# PD_MK2_Connectors.net
KiCad netlist of a schematic drawn in Altium Designer
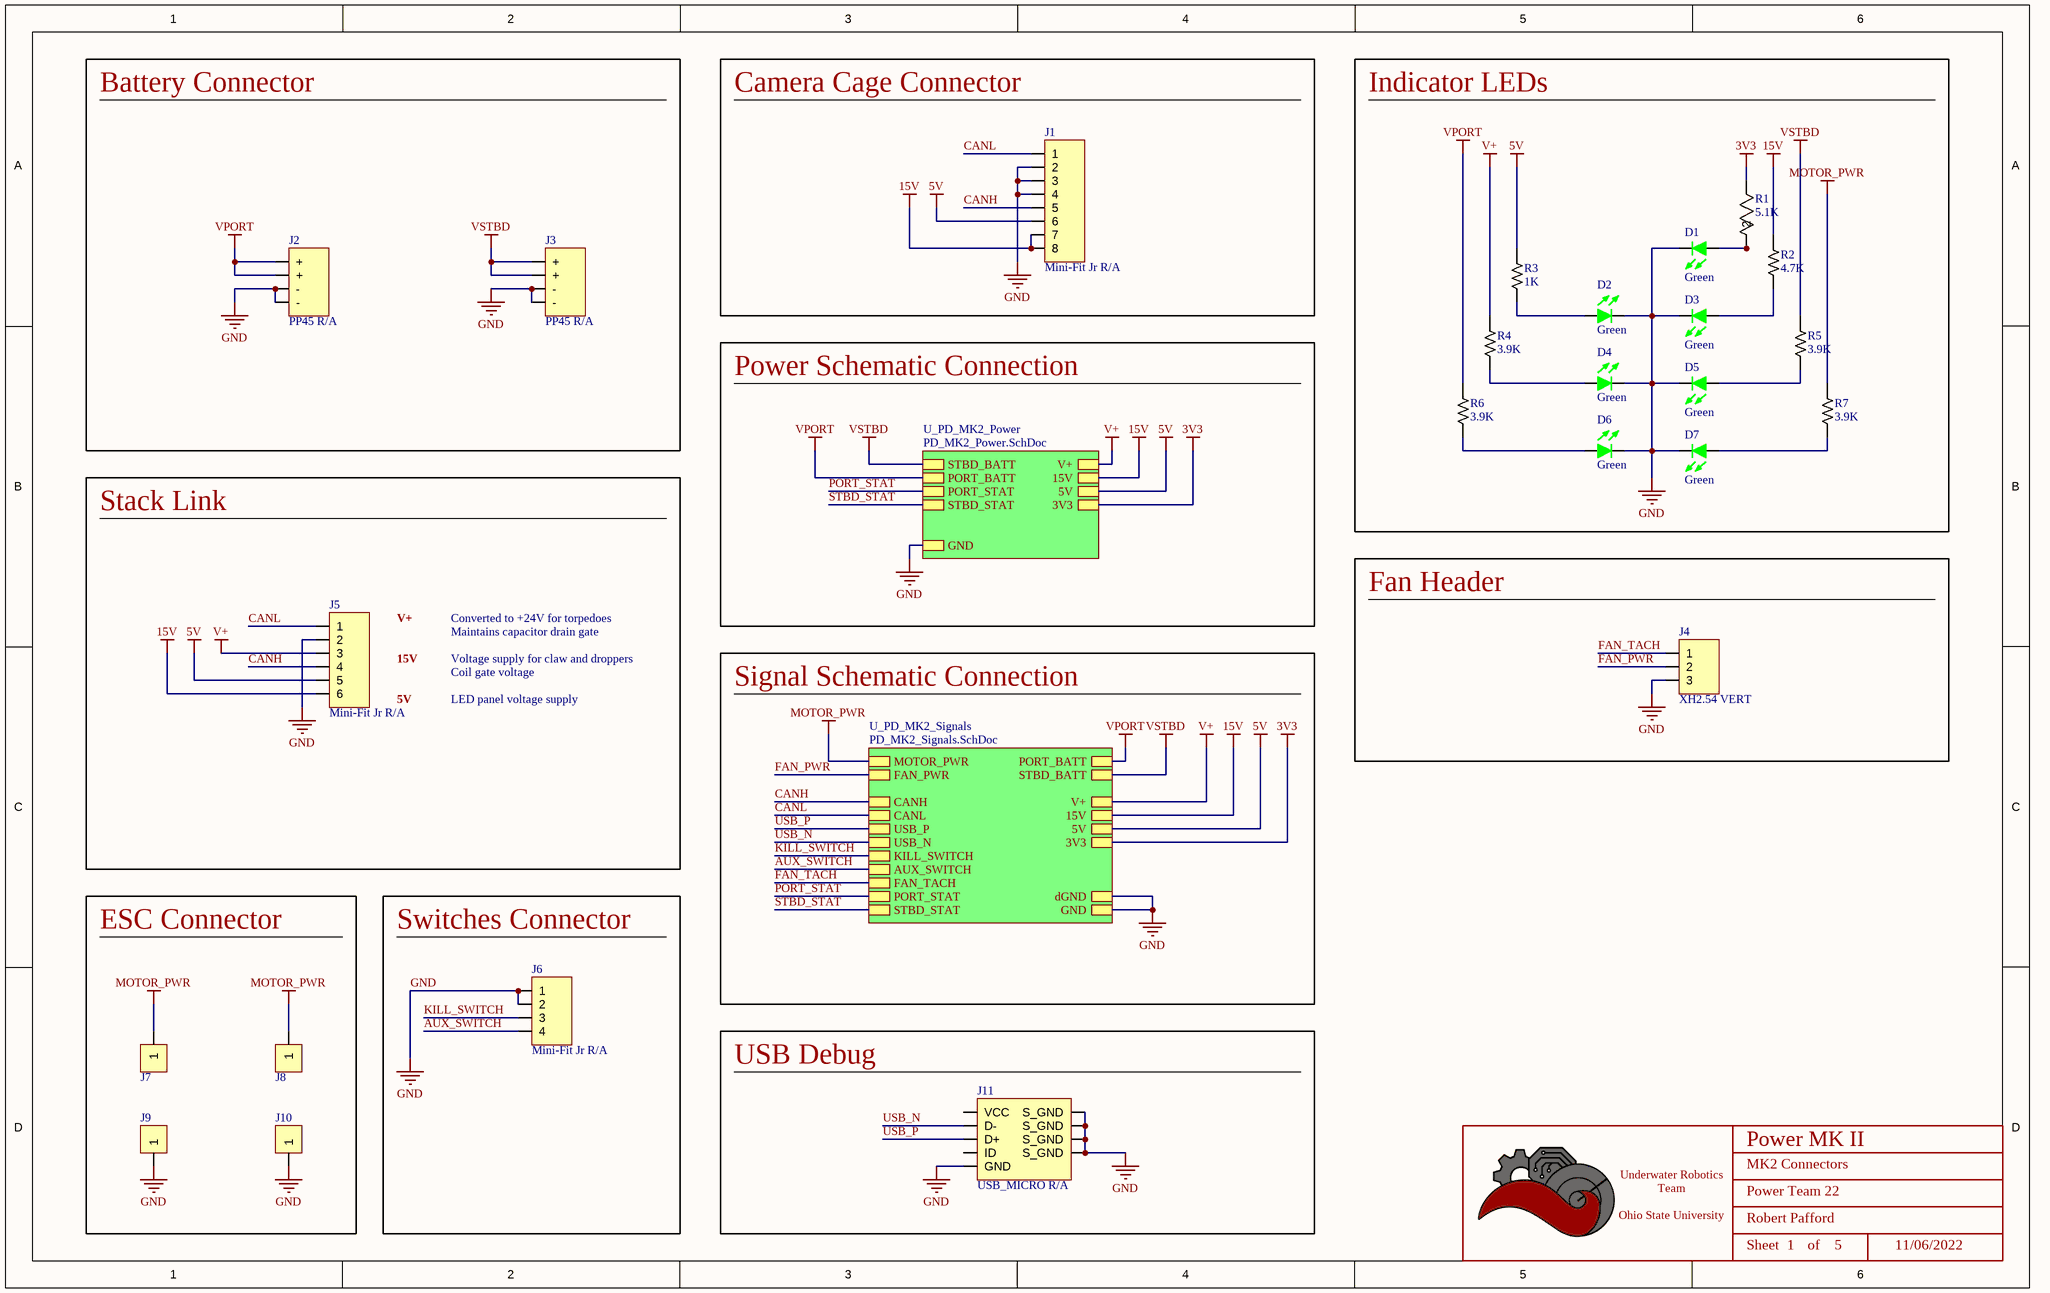
[diagram p0: PD_MK2_Connectors.SchDoc]

(export (version "E")
  (design (tool "Eeschema 10.0.6"))
  (components
    (comp (ref "D1")
      (value "IN-S63AT5G")
      (footprint "LED_0603")
      (description "LED Green Vf= 3V If = 0.005A\r\nIN-S63AT5G")
      (fields (field (name "COLOR") "Green") (field (name "MADE BY") "Robert Pafford"))
      (libsource (lib "Diodes") (part "LED_Green_0603_3V"))
    )
    (comp (ref "D2")
      (value "IN-S63AT5G")
      (footprint "LED_0603")
      (description "LED Green Vf= 3V If = 0.005A\r\nIN-S63AT5G")
      (fields (field (name "COLOR") "Green") (field (name "MADE BY") "Robert Pafford"))
      (libsource (lib "Diodes") (part "LED_Green_0603_3V"))
    )
    (comp (ref "D3")
      (value "IN-S63AT5G")
      (footprint "LED_0603")
      (description "LED Green Vf= 3V If = 0.005A\r\nIN-S63AT5G")
      (fields (field (name "COLOR") "Green") (field (name "MADE BY") "Robert Pafford"))
      (libsource (lib "Diodes") (part "LED_Green_0603_3V"))
    )
    (comp (ref "D4")
      (value "IN-S63AT5G")
      (footprint "LED_0603")
      (description "LED Green Vf= 3V If = 0.005A\r\nIN-S63AT5G")
      (fields (field (name "COLOR") "Green") (field (name "MADE BY") "Robert Pafford"))
      (libsource (lib "Diodes") (part "LED_Green_0603_3V"))
    )
    (comp (ref "D5")
      (value "IN-S63AT5G")
      (footprint "LED_0603")
      (description "LED Green Vf= 3V If = 0.005A\r\nIN-S63AT5G")
      (fields (field (name "COLOR") "Green") (field (name "MADE BY") "Robert Pafford"))
      (libsource (lib "Diodes") (part "LED_Green_0603_3V"))
    )
    (comp (ref "D6")
      (value "IN-S63AT5G")
      (footprint "LED_0603")
      (description "LED Green Vf= 3V If = 0.005A\r\nIN-S63AT5G")
      (fields (field (name "COLOR") "Green") (field (name "MADE BY") "Robert Pafford"))
      (libsource (lib "Diodes") (part "LED_Green_0603_3V"))
    )
    (comp (ref "D7")
      (value "IN-S63AT5G")
      (footprint "LED_0603")
      (description "LED Green Vf= 3V If = 0.005A\r\nIN-S63AT5G")
      (fields (field (name "COLOR") "Green") (field (name "MADE BY") "Robert Pafford"))
      (libsource (lib "Diodes") (part "LED_Green_0603_3V"))
    )
    (comp (ref "J1")
      (value "Mini-Fit Jr R/A")
      (footprint "CONN_MOLEX_MINIFIT JR_8 POS_R/A")
      (description "Molex Minifit Jr. 5569 \r\n8 Pos R/A Natural")
      (fields (field (name "MANUFACTURER") "Molex") (field (name "CREATED BY") "Flip B"))
      (libsource (lib "Connectors") (part "CONN_MOLEX_MINIFIT JR_8POS_R/A"))
    )
    (comp (ref "J2")
      (value "PP45 R/A")
      (footprint "CONN_ANDERSON_PP45_4 POS_R/A")
      (description "Anderson PP45\r\n4 Pos R/A Red/Black")
      (fields (field (name "MANUFACTURER") "Anderson") (field (name "CREATED BY") "Flip B"))
      (libsource (lib "Connectors") (part "CONN_ANDERSON_2x2_R/A"))
    )
    (comp (ref "J3")
      (value "PP45 R/A")
      (footprint "CONN_ANDERSON_PP45_4 POS_R/A")
      (description "Anderson PP45\r\n4 Pos R/A Red/Black")
      (fields (field (name "MANUFACTURER") "Anderson") (field (name "CREATED BY") "Flip B"))
      (libsource (lib "Connectors") (part "CONN_ANDERSON_2x2_R/A"))
    )
    (comp (ref "J4")
      (value "XH2.54 VERT")
      (footprint "CONN_JST_XH254_3POS_VERT")
      (description "JST XH 2.54mm Pitch 3 Pos Vertical")
      (fields (field (name "MANUFACTURER") "JST") (field (name "CREATED BY") "Robert P"))
      (libsource (lib "Connectors") (part "CONN_JST_XH254_3POS_VERT"))
    )
    (comp (ref "J5")
      (value "Mini-Fit Jr R/A")
      (footprint "CONN_MOLEX_MINIFIT JR_6 POS_R/A")
      (description "Molex Minifit Jr. 5569 \r\n6 Pos R/A Natural")
      (fields (field (name "MANUFACTURER") "Molex") (field (name "CREATED BY") "Flip B"))
      (libsource (lib "Connectors") (part "CONN_MOLEX_MINIFIT JR_6POS_R/A"))
    )
    (comp (ref "J6")
      (value "Mini-Fit Jr R/A")
      (footprint "CONN_MOLEX_MINIFIT JR_4 POS_R/A")
      (description "Molex Minifit Jr. 5569 \r\n4 Pos R/A Natural")
      (fields (field (name "MANUFACTURER") "Molex") (field (name "CREATED BY") "Flip B"))
      (libsource (lib "Connectors") (part "CONN_MOLEX_MINIFIT JR_4POS_R/A"))
    )
    (comp (ref "J7")
      (value "Redcube M4 Term 85A")
      (footprint "Redcube M4 Term 85A")
      (fields (field (name "CREATED BY") "Nahtan Ayer"))
      (libsource (lib "") (part "Redcube M4 Term 85A_1"))
    )
    (comp (ref "J8")
      (value "Redcube M4 Term 85A")
      (footprint "Redcube M4 Term 85A")
      (fields (field (name "CREATED BY") "Nahtan Ayer"))
      (libsource (lib "") (part "Redcube M4 Term 85A_1"))
    )
    (comp (ref "J9")
      (value "Redcube M4 Term 85A")
      (footprint "Redcube M4 Term 85A")
      (fields (field (name "CREATED BY") "Nahtan Ayer"))
      (libsource (lib "Connectors") (part "Redcube M4 Term 85A"))
    )
    (comp (ref "J10")
      (value "Redcube M4 Term 85A")
      (footprint "Redcube M4 Term 85A")
      (fields (field (name "CREATED BY") "Nahtan Ayer"))
      (libsource (lib "Connectors") (part "Redcube M4 Term 85A"))
    )
    (comp (ref "J11")
      (value "USB_MICRO R/A")
      (footprint "CONN_MINIUSB")
      (description "Amphenol Micro USB-B\r\nUSB2.0 5 Pin Right Angle SMD")
      (fields (field (name "MANUFACTURER") "Amphenol") (field (name "CREATED BY") "Flip B"))
      (libsource (lib "Connectors") (part "CONN_MICROUSB"))
    )
    (comp (ref "R1")
      (value "5.1K")
      (footprint "RC0603N_PAN")
      (description "5.1 kOhms ±0.1% 0.1W, 1/10W Chip Resistor 0603 (1608 Metric) Automotive AEC-Q200 Thin Film")
      (fields
        (field (name "MANUFACTURER_PART_NUMBER") "ERA-3AEB512V_2")
        (field (name "COPYRIGHT") "Copyright (C) 2023 Ultra Librarian. All rights reserved.")
      )
      (libsource (lib "Resistors") (part "ERA-3AEB512V_2"))
    )
    (comp (ref "R2")
      (value "4.7k Ohm 5% 1/10W")
      (footprint "RESISTOR_0603")
      (description "RES 4.7k OHM 5% 1/10W 0603")
      (fields
        (field (name "TOLERANCE") "+/- 5%")
        (field (name "VALUE  (OHMS)") "4.7K")
        (field (name "MADE BY") "Robert Pafford")
      )
      (libsource (lib "Resistors") (part "RESISTOR_4.7K_0603"))
    )
    (comp (ref "R3")
      (value "1k Ohm 5% 1/8W")
      (footprint "RESISTOR_0603")
      (description "RES 1k OHM 5% 1/8W 0603")
      (fields
        (field (name "TOLERANCE") "+/- 5%")
        (field (name "VALUE  (OHMS)") "1K")
        (field (name "MADE BY") "Robert Pafford")
      )
      (libsource (lib "Resistors") (part "RESISTOR_1K_0603"))
    )
    (comp (ref "R4")
      (value "3.9k Ohm 5% 1/10W")
      (footprint "RESISTOR_0603")
      (description "RES 3.9k OHM 1% 1/10W 0603")
      (fields
        (field (name "TOLERANCE") "+/- 1%")
        (field (name "VALUE  (OHMS)") "3.9K")
        (field (name "MADE BY") "Robert Pafford")
      )
      (libsource (lib "Resistors") (part "RESISTOR_3.9K_0603"))
    )
    (comp (ref "R5")
      (value "3.9k Ohm 5% 1/10W")
      (footprint "RESISTOR_0603")
      (description "RES 3.9k OHM 1% 1/10W 0603")
      (fields
        (field (name "TOLERANCE") "+/- 1%")
        (field (name "VALUE  (OHMS)") "3.9K")
        (field (name "MADE BY") "Robert Pafford")
      )
      (libsource (lib "Resistors") (part "RESISTOR_3.9K_0603"))
    )
    (comp (ref "R6")
      (value "3.9k Ohm 5% 1/10W")
      (footprint "RESISTOR_0603")
      (description "RES 3.9k OHM 1% 1/10W 0603")
      (fields
        (field (name "TOLERANCE") "+/- 1%")
        (field (name "VALUE  (OHMS)") "3.9K")
        (field (name "MADE BY") "Robert Pafford")
      )
      (libsource (lib "Resistors") (part "RESISTOR_3.9K_0603"))
    )
    (comp (ref "R7")
      (value "3.9k Ohm 5% 1/10W")
      (footprint "RESISTOR_0603")
      (description "RES 3.9k OHM 1% 1/10W 0603")
      (fields
        (field (name "TOLERANCE") "+/- 1%")
        (field (name "VALUE  (OHMS)") "3.9K")
        (field (name "MADE BY") "Robert Pafford")
      )
      (libsource (lib "Resistors") (part "RESISTOR_3.9K_0603"))
    )
  )
  (nets
    (net (code "1") (name "/AUX_SWITCH") (class "Default")
      (node (ref "J6") (pin "4") (pinfunction "4_4") (pintype "passive"))
    )
    (net (code "2") (name "/CANH") (class "Default")
      (node (ref "J1") (pin "5") (pinfunction "5_5") (pintype "passive"))
      (node (ref "J5") (pin "4") (pinfunction "4_4") (pintype "passive"))
    )
    (net (code "3") (name "/CANL") (class "Default")
      (node (ref "J1") (pin "1") (pinfunction "1_1") (pintype "passive"))
      (node (ref "J5") (pin "1") (pinfunction "1_1") (pintype "passive"))
    )
    (net (code "4") (name "/FAN_PWR") (class "Default")
      (node (ref "J4") (pin "2") (pinfunction "2_2") (pintype "passive"))
    )
    (net (code "5") (name "/FAN_TACH") (class "Default")
      (node (ref "J4") (pin "1") (pinfunction "1_1") (pintype "passive"))
    )
    (net (code "6") (name "/KILL_SWITCH") (class "Default")
      (node (ref "J6") (pin "3") (pinfunction "3_3") (pintype "passive"))
    )
    (net (code "9") (name "/USB_N") (class "Default")
      (node (ref "J11") (pin "2") (pinfunction "D-_2") (pintype "passive"))
    )
    (net (code "10") (name "/USB_P") (class "Default")
      (node (ref "J11") (pin "3") (pinfunction "D+_3") (pintype "passive"))
    )
    (net (code "11") (name "3V3") (class "Default")
      (node (ref "R1") (pin "1") (pinfunction "1_1") (pintype "passive"))
    )
    (net (code "12") (name "5V") (class "Default")
      (node (ref "J1") (pin "6") (pinfunction "6_6") (pintype "passive"))
      (node (ref "J5") (pin "5") (pinfunction "5_5") (pintype "passive"))
      (node (ref "R3") (pin "1") (pinfunction "1_1") (pintype "passive"))
    )
    (net (code "13") (name "15V") (class "Default")
      (node (ref "J1") (pin "7") (pinfunction "7_7") (pintype "passive"))
      (node (ref "J1") (pin "8") (pinfunction "8_8") (pintype "passive"))
      (node (ref "J5") (pin "6") (pinfunction "6_6") (pintype "passive"))
      (node (ref "R2") (pin "1") (pinfunction "1_1") (pintype "passive"))
    )
    (net (code "14") (name "GND") (class "Default")
      (node (ref "D1") (pin "2") (pinfunction "2_2") (pintype "passive"))
      (node (ref "D2") (pin "2") (pinfunction "2_2") (pintype "passive"))
      (node (ref "D3") (pin "2") (pinfunction "2_2") (pintype "passive"))
      (node (ref "D4") (pin "2") (pinfunction "2_2") (pintype "passive"))
      (node (ref "D5") (pin "2") (pinfunction "2_2") (pintype "passive"))
      (node (ref "D6") (pin "2") (pinfunction "2_2") (pintype "passive"))
      (node (ref "D7") (pin "2") (pinfunction "2_2") (pintype "passive"))
      (node (ref "J1") (pin "2") (pinfunction "2_2") (pintype "passive"))
      (node (ref "J1") (pin "3") (pinfunction "3_3") (pintype "passive"))
      (node (ref "J1") (pin "4") (pinfunction "4_4") (pintype "passive"))
      (node (ref "J10") (pin "1") (pinfunction "1_1") (pintype "passive"))
      (node (ref "J11") (pin "5") (pinfunction "GND_5") (pintype "passive"))
      (node (ref "J11") (pin "6") (pinfunction "S_GND_6") (pintype "passive"))
      (node (ref "J11") (pin "7") (pinfunction "S_GND_7") (pintype "passive"))
      (node (ref "J11") (pin "8") (pinfunction "S_GND_8") (pintype "passive"))
      (node (ref "J11") (pin "9") (pinfunction "S_GND_9") (pintype "passive"))
      (node (ref "J2") (pin "3") (pinfunction "-_3") (pintype "passive"))
      (node (ref "J2") (pin "4") (pinfunction "-_4") (pintype "passive"))
      (node (ref "J3") (pin "3") (pinfunction "-_3") (pintype "passive"))
      (node (ref "J3") (pin "4") (pinfunction "-_4") (pintype "passive"))
      (node (ref "J4") (pin "3") (pinfunction "3_3") (pintype "passive"))
      (node (ref "J5") (pin "2") (pinfunction "2_2") (pintype "passive"))
      (node (ref "J6") (pin "1") (pinfunction "1_1") (pintype "passive"))
      (node (ref "J6") (pin "2") (pinfunction "2_2") (pintype "passive"))
      (node (ref "J9") (pin "1") (pinfunction "1_1") (pintype "passive"))
    )
    (net (code "15") (name "MOTOR_PWR") (class "Default")
      (node (ref "J7") (pin "1") (pinfunction "1_1") (pintype "passive"))
      (node (ref "J8") (pin "1") (pinfunction "1_1") (pintype "passive"))
      (node (ref "R7") (pin "1") (pinfunction "1_1") (pintype "passive"))
    )
    (net (code "16") (name "Net-(D1-Pad1)") (class "Default")
      (node (ref "D1") (pin "1") (pinfunction "1_1") (pintype "passive"))
      (node (ref "R1") (pin "2") (pinfunction "2_2") (pintype "passive"))
    )
    (net (code "17") (name "Net-(D2-Pad1)") (class "Default")
      (node (ref "D2") (pin "1") (pinfunction "1_1") (pintype "passive"))
      (node (ref "R3") (pin "2") (pinfunction "2_2") (pintype "passive"))
    )
    (net (code "18") (name "Net-(D3-Pad1)") (class "Default")
      (node (ref "D3") (pin "1") (pinfunction "1_1") (pintype "passive"))
      (node (ref "R2") (pin "2") (pinfunction "2_2") (pintype "passive"))
    )
    (net (code "19") (name "Net-(D4-Pad1)") (class "Default")
      (node (ref "D4") (pin "1") (pinfunction "1_1") (pintype "passive"))
      (node (ref "R4") (pin "2") (pinfunction "2_2") (pintype "passive"))
    )
    (net (code "20") (name "Net-(D5-Pad1)") (class "Default")
      (node (ref "D5") (pin "1") (pinfunction "1_1") (pintype "passive"))
      (node (ref "R5") (pin "2") (pinfunction "2_2") (pintype "passive"))
    )
    (net (code "21") (name "Net-(D6-Pad1)") (class "Default")
      (node (ref "D6") (pin "1") (pinfunction "1_1") (pintype "passive"))
      (node (ref "R6") (pin "2") (pinfunction "2_2") (pintype "passive"))
    )
    (net (code "22") (name "Net-(D7-Pad1)") (class "Default")
      (node (ref "D7") (pin "1") (pinfunction "1_1") (pintype "passive"))
      (node (ref "R7") (pin "2") (pinfunction "2_2") (pintype "passive"))
    )
    (net (code "23") (name "V+") (class "Default")
      (node (ref "J5") (pin "3") (pinfunction "3_3") (pintype "passive"))
      (node (ref "R4") (pin "1") (pinfunction "1_1") (pintype "passive"))
    )
    (net (code "24") (name "VPORT") (class "Default")
      (node (ref "J2") (pin "1") (pinfunction "+_1") (pintype "passive"))
      (node (ref "J2") (pin "2") (pinfunction "+_2") (pintype "passive"))
      (node (ref "R6") (pin "1") (pinfunction "1_1") (pintype "passive"))
    )
    (net (code "25") (name "VSTBD") (class "Default")
      (node (ref "J3") (pin "1") (pinfunction "+_1") (pintype "passive"))
      (node (ref "J3") (pin "2") (pinfunction "+_2") (pintype "passive"))
      (node (ref "R5") (pin "1") (pinfunction "1_1") (pintype "passive"))
    )
    (net (code "26") (name "unconnected-(J11-ID-Pad4)") (class "Default")
      (node (ref "J11") (pin "4") (pinfunction "ID_4") (pintype "passive"))
    )
    (net (code "27") (name "unconnected-(J11-VCC-Pad1)") (class "Default")
      (node (ref "J11") (pin "1") (pinfunction "VCC_1") (pintype "passive"))
    )
  )
)
